# Laskuri.net
KiCad netlist of a schematic drawn in EAGLE
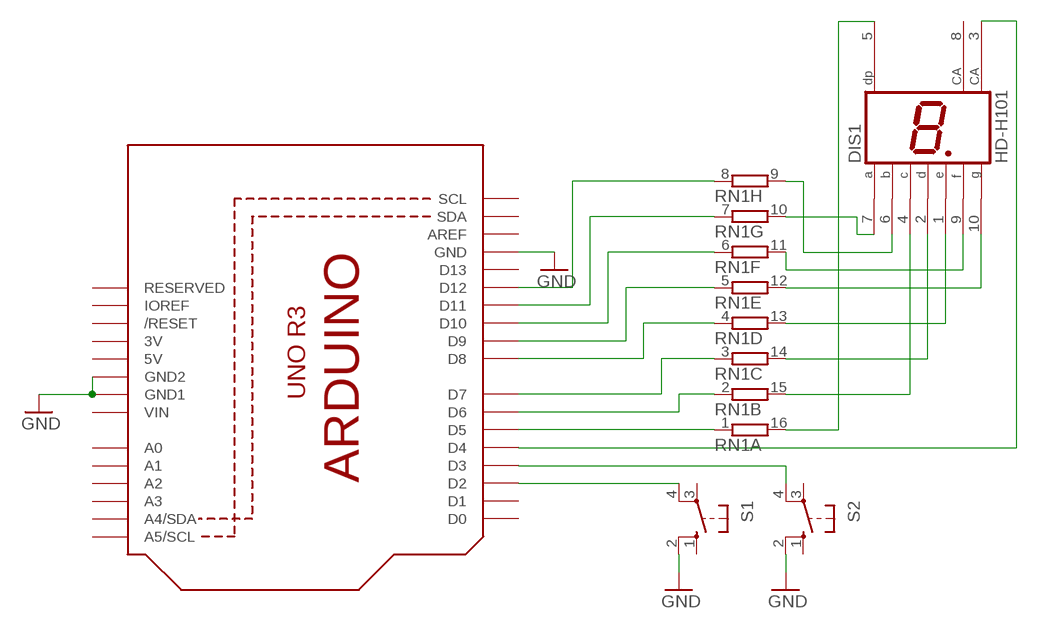
[diagram p0: schematic, sheet 1]

(export (version "E")
  (design (tool "Eeschema 10.0.6"))
  (components
    (comp (ref "DIS1")
      (value "HD-H101")
      (footprint "eagle-import:HDSP-M")
      (libsource (lib "eagle-import") (part "HD-H101"))
    )
    (comp (ref "RN1")
      (value "8R-N")
      (footprint "eagle-import:DIL16")
      (libsource (lib "eagle-import") (part "8R-N"))
    )
    (comp (ref "S1")
      (value "10-XX")
      (footprint "eagle-import:B3F-10XX")
      (fields (field (name "MPN") "B3F-1000"))
      (libsource (lib "eagle-import") (part "10-XX"))
    )
    (comp (ref "S2")
      (value "10-XX")
      (footprint "eagle-import:B3F-10XX")
      (fields (field (name "MPN") "B3F-1000"))
      (libsource (lib "eagle-import") (part "10-XX"))
    )
    (comp (ref "U1")
      (value "ARDUINOR3-DIMENSION")
      (footprint "eagle-import:ARDUINOR3")
      (libsource (lib "eagle-import") (part "ARDUINOR3-DIMENSION"))
    )
  )
  (nets
    (net (code "1") (name "/3V") (class "Default")
      (node (ref "U1") (pin "3V") (pinfunction "3V_3V") (pintype "power_in"))
    )
    (net (code "2") (name "/5V") (class "Default")
      (node (ref "U1") (pin "5V") (pinfunction "5V_5V") (pintype "power_in"))
    )
    (net (code "3") (name "/VIN") (class "Default")
      (node (ref "U1") (pin "VIN") (pinfunction "VIN_VIN") (pintype "power_in"))
    )
    (net (code "4") (name "GND") (class "Default")
      (node (ref "S1") (pin "2") (pinfunction "S1_2") (pintype "passive"))
      (node (ref "S2") (pin "2") (pinfunction "S1_2") (pintype "passive"))
      (node (ref "U1") (pin "GND") (pinfunction "GND_GND") (pintype "power_in"))
      (node (ref "U1") (pin "GND1") (pinfunction "GND1_GND1") (pintype "power_in"))
      (node (ref "U1") (pin "GND2") (pinfunction "GND2_GND2") (pintype "power_in"))
    )
    (net (code "5") (name "Net-(DIS1-A)") (class "Default")
      (node (ref "DIS1") (pin "7") (pinfunction "A_7") (pintype "passive"))
      (node (ref "RN1") (pin "10") (pinfunction "2_10") (pintype "passive"))
    )
    (net (code "6") (name "Net-(DIS1-B)") (class "Default")
      (node (ref "DIS1") (pin "6") (pinfunction "B_6") (pintype "passive"))
      (node (ref "RN1") (pin "9") (pinfunction "2_9") (pintype "passive"))
    )
    (net (code "7") (name "Net-(DIS1-C)") (class "Default")
      (node (ref "DIS1") (pin "4") (pinfunction "C_4") (pintype "passive"))
      (node (ref "RN1") (pin "15") (pinfunction "2_15") (pintype "passive"))
    )
    (net (code "8") (name "Net-(DIS1-CA-Pad3)") (class "Default")
      (node (ref "DIS1") (pin "3") (pinfunction "CA_3") (pintype "passive"))
      (node (ref "U1") (pin "D4") (pinfunction "D4_D4") (pintype "bidirectional"))
    )
    (net (code "9") (name "Net-(DIS1-D)") (class "Default")
      (node (ref "DIS1") (pin "2") (pinfunction "D_2") (pintype "passive"))
      (node (ref "RN1") (pin "14") (pinfunction "2_14") (pintype "passive"))
    )
    (net (code "10") (name "Net-(DIS1-DP)") (class "Default")
      (node (ref "DIS1") (pin "5") (pinfunction "DP_5") (pintype "passive"))
      (node (ref "RN1") (pin "16") (pinfunction "2_16") (pintype "passive"))
    )
    (net (code "11") (name "Net-(DIS1-E)") (class "Default")
      (node (ref "DIS1") (pin "1") (pinfunction "E_1") (pintype "passive"))
      (node (ref "RN1") (pin "13") (pinfunction "2_13") (pintype "passive"))
    )
    (net (code "12") (name "Net-(DIS1-F)") (class "Default")
      (node (ref "DIS1") (pin "9") (pinfunction "F_9") (pintype "passive"))
      (node (ref "RN1") (pin "11") (pinfunction "2_11") (pintype "passive"))
    )
    (net (code "13") (name "Net-(DIS1-G)") (class "Default")
      (node (ref "DIS1") (pin "10") (pinfunction "G_10") (pintype "passive"))
      (node (ref "RN1") (pin "12") (pinfunction "2_12") (pintype "passive"))
    )
    (net (code "14") (name "Net-(RN1-Pad1)") (class "Default")
      (node (ref "RN1") (pin "1") (pinfunction "1_1") (pintype "passive"))
      (node (ref "U1") (pin "D5") (pinfunction "D5_D5") (pintype "bidirectional"))
    )
    (net (code "15") (name "Net-(RN1B-1)") (class "Default")
      (node (ref "RN1") (pin "2") (pinfunction "1_2") (pintype "passive"))
      (node (ref "U1") (pin "D6") (pinfunction "D6_D6") (pintype "bidirectional"))
    )
    (net (code "16") (name "Net-(RN1C-1)") (class "Default")
      (node (ref "RN1") (pin "3") (pinfunction "1_3") (pintype "passive"))
      (node (ref "U1") (pin "D7") (pinfunction "D7_D7") (pintype "bidirectional"))
    )
    (net (code "17") (name "Net-(RN1D-1)") (class "Default")
      (node (ref "RN1") (pin "4") (pinfunction "1_4") (pintype "passive"))
      (node (ref "U1") (pin "D8") (pinfunction "D8_D8") (pintype "bidirectional"))
    )
    (net (code "18") (name "Net-(RN1E-1)") (class "Default")
      (node (ref "RN1") (pin "5") (pinfunction "1_5") (pintype "passive"))
      (node (ref "U1") (pin "D9") (pinfunction "D9_D9") (pintype "bidirectional"))
    )
    (net (code "19") (name "Net-(RN1F-1)") (class "Default")
      (node (ref "RN1") (pin "6") (pinfunction "1_6") (pintype "passive"))
      (node (ref "U1") (pin "D10") (pinfunction "D10_D10") (pintype "bidirectional"))
    )
    (net (code "20") (name "Net-(RN1G-1)") (class "Default")
      (node (ref "RN1") (pin "7") (pinfunction "1_7") (pintype "passive"))
      (node (ref "U1") (pin "D11") (pinfunction "D11_D11") (pintype "bidirectional"))
    )
    (net (code "21") (name "Net-(RN1H-1)") (class "Default")
      (node (ref "RN1") (pin "8") (pinfunction "1_8") (pintype "passive"))
      (node (ref "U1") (pin "D12") (pinfunction "D12_D12") (pintype "bidirectional"))
    )
    (net (code "22") (name "Net-(S1-P1)") (class "Default")
      (node (ref "S1") (pin "4") (pinfunction "P1_4") (pintype "passive"))
      (node (ref "U1") (pin "D2") (pinfunction "D2_D2") (pintype "bidirectional"))
    )
    (net (code "23") (name "Net-(S2-P1)") (class "Default")
      (node (ref "S2") (pin "4") (pinfunction "P1_4") (pintype "passive"))
      (node (ref "U1") (pin "D3") (pinfunction "D3_D3") (pintype "bidirectional"))
    )
    (net (code "24") (name "unconnected-(DIS1-CA-Pad8)") (class "Default")
      (node (ref "DIS1") (pin "8") (pinfunction "CA_8") (pintype "passive"))
    )
    (net (code "25") (name "unconnected-(S1-P-Pad3)") (class "Default")
      (node (ref "S1") (pin "3") (pinfunction "P_3") (pintype "passive"))
    )
    (net (code "26") (name "unconnected-(S1-S-Pad1)") (class "Default")
      (node (ref "S1") (pin "1") (pinfunction "S_1") (pintype "passive"))
    )
    (net (code "27") (name "unconnected-(S2-P-Pad3)") (class "Default")
      (node (ref "S2") (pin "3") (pinfunction "P_3") (pintype "passive"))
    )
    (net (code "28") (name "unconnected-(S2-S-Pad1)") (class "Default")
      (node (ref "S2") (pin "1") (pinfunction "S_1") (pintype "passive"))
    )
    (net (code "29") (name "unconnected-(U1-A4{slash}SDA-PadA4)") (class "Default")
      (node (ref "U1") (pin "A4") (pinfunction "A4/SDA_A4") (pintype "bidirectional"))
    )
    (net (code "30") (name "unconnected-(U1-A5{slash}SCL-PadA5)") (class "Default")
      (node (ref "U1") (pin "A5") (pinfunction "A5/SCL_A5") (pintype "bidirectional"))
    )
    (net (code "31") (name "unconnected-(U1-PadA0)") (class "Default")
      (node (ref "U1") (pin "A0") (pinfunction "A0_A0") (pintype "bidirectional"))
    )
    (net (code "32") (name "unconnected-(U1-PadA1)") (class "Default")
      (node (ref "U1") (pin "A1") (pinfunction "A1_A1") (pintype "bidirectional"))
    )
    (net (code "33") (name "unconnected-(U1-PadA2)") (class "Default")
      (node (ref "U1") (pin "A2") (pinfunction "A2_A2") (pintype "bidirectional"))
    )
    (net (code "34") (name "unconnected-(U1-PadA3)") (class "Default")
      (node (ref "U1") (pin "A3") (pinfunction "A3_A3") (pintype "bidirectional"))
    )
    (net (code "35") (name "unconnected-(U1-PadAREF)") (class "Default")
      (node (ref "U1") (pin "AREF") (pinfunction "AREF_AREF") (pintype "bidirectional"))
    )
    (net (code "36") (name "unconnected-(U1-PadD0)") (class "Default")
      (node (ref "U1") (pin "D0") (pinfunction "D0_D0") (pintype "bidirectional"))
    )
    (net (code "37") (name "unconnected-(U1-PadD1)") (class "Default")
      (node (ref "U1") (pin "D1") (pinfunction "D1_D1") (pintype "bidirectional"))
    )
    (net (code "38") (name "unconnected-(U1-PadD13)") (class "Default")
      (node (ref "U1") (pin "D13") (pinfunction "D13_D13") (pintype "bidirectional"))
    )
    (net (code "39") (name "unconnected-(U1-PadIOREF)") (class "Default")
      (node (ref "U1") (pin "IOREF") (pinfunction "IOREF_IOREF") (pintype "output"))
    )
    (net (code "40") (name "unconnected-(U1-PadRESERVED)") (class "Default")
      (node (ref "U1") (pin "RESERVED") (pinfunction "RESERVED_RESERVED") (pintype "no_connect"))
    )
    (net (code "41") (name "unconnected-(U1-PadSCL)") (class "Default")
      (node (ref "U1") (pin "SCL") (pinfunction "SCL_SCL") (pintype "bidirectional"))
    )
    (net (code "42") (name "unconnected-(U1-PadSDA)") (class "Default")
      (node (ref "U1") (pin "SDA") (pinfunction "SDA_SDA") (pintype "bidirectional"))
    )
    (net (code "43") (name "unconnected-(U1-{slash}RESET-PadRESET)") (class "Default")
      (node (ref "U1") (pin "RESET") (pinfunction "/RESET_RESET") (pintype "bidirectional"))
    )
  )
)
